# Marklin_BR_128_21MTC_Adapter.net
KiCad netlist of a schematic drawn in EAGLE
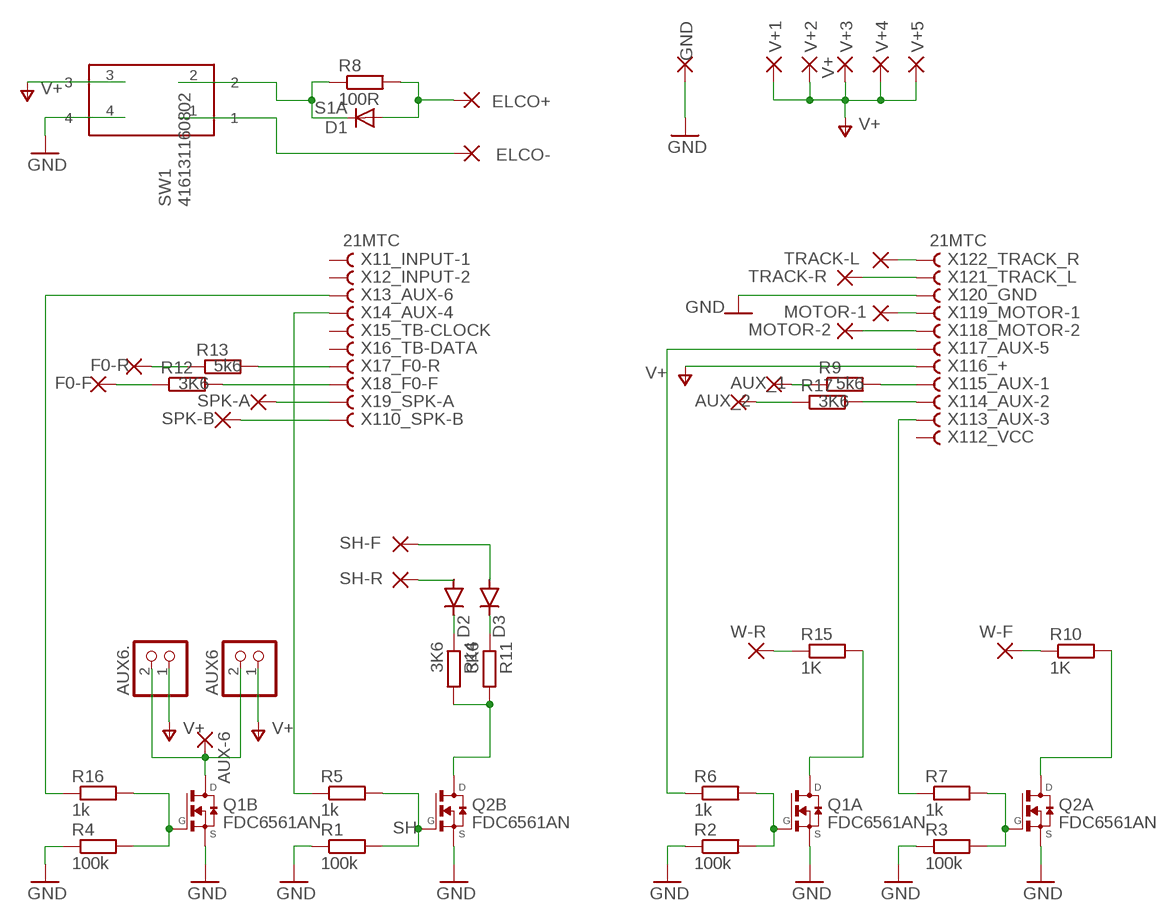
[diagram p0: schematic, sheet 1]

(export (version "E")
  (design (tool "Eeschema 10.0.6"))
  (components
    (comp (ref "AUX-6")
      (value "SMD2")
      (footprint "eagle-import:SMD1,27-2,54")
      (libsource (lib "eagle-import") (part "SMD2"))
    )
    (comp (ref "AUX6")
      (value "JST_2PIN-THM-RA")
      (footprint "eagle-import:JST-PH-2-THM-RA")
      (libsource (lib "eagle-import") (part "JST_2PIN-THM-RA"))
    )
    (comp (ref "AUX6.")
      (value "JST_2PIN-THM-RA")
      (footprint "eagle-import:JST-PH-2-THM-RA")
      (libsource (lib "eagle-import") (part "JST_2PIN-THM-RA"))
    )
    (comp (ref "AUX_1")
      (value "SMD2")
      (footprint "eagle-import:SMD1,27-2,54")
      (libsource (lib "eagle-import") (part "SMD2"))
    )
    (comp (ref "AUX_2")
      (value "SMD2")
      (footprint "eagle-import:SMD1,27-2,54")
      (libsource (lib "eagle-import") (part "SMD2"))
    )
    (comp (ref "D1")
      (value "S1A")
      (footprint "eagle-import:DO214AC")
      (fields (field (name "MF") "Fairchild"))
      (libsource (lib "eagle-import") (part "S1A"))
    )
    (comp (ref "D2")
      (value "S1M")
      (footprint "eagle-import:SMA")
      (libsource (lib "eagle-import") (part "S1M"))
    )
    (comp (ref "D3")
      (value "S1M")
      (footprint "eagle-import:SMA")
      (libsource (lib "eagle-import") (part "S1M"))
    )
    (comp (ref "ELCO+")
      (value "SMD2")
      (footprint "eagle-import:SMD1,27-2,54")
      (libsource (lib "eagle-import") (part "SMD2"))
    )
    (comp (ref "ELCO-")
      (value "SMD2")
      (footprint "eagle-import:SMD1,27-2,54")
      (libsource (lib "eagle-import") (part "SMD2"))
    )
    (comp (ref "F0-F")
      (value "SMD2")
      (footprint "eagle-import:SMD1,27-2,54")
      (libsource (lib "eagle-import") (part "SMD2"))
    )
    (comp (ref "F0-R")
      (value "SMD2")
      (footprint "eagle-import:SMD1,27-2,54")
      (libsource (lib "eagle-import") (part "SMD2"))
    )
    (comp (ref "GND")
      (value "SMD2")
      (footprint "eagle-import:SMD1,27-2,54")
      (libsource (lib "eagle-import") (part "SMD2"))
    )
    (comp (ref "MOTOR-1")
      (value "SMD2")
      (footprint "eagle-import:SMD1,27-2,54")
      (libsource (lib "eagle-import") (part "SMD2"))
    )
    (comp (ref "MOTOR-2")
      (value "SMD2")
      (footprint "eagle-import:SMD1,27-2,54")
      (libsource (lib "eagle-import") (part "SMD2"))
    )
    (comp (ref "Q1")
      (value "FDC6561AN")
      (footprint "eagle-import:SSOT-6")
      (fields (field (name "DIGI-KEY_PART_NUMBER") "FDC6561ANCT-ND") (field (name "MF") "ON Semiconductor"))
      (libsource (lib "eagle-import") (part "FDC6561AN"))
    )
    (comp (ref "Q2")
      (value "FDC6561AN")
      (footprint "eagle-import:SSOT-6")
      (fields (field (name "DIGI-KEY_PART_NUMBER") "FDC6561ANCT-ND") (field (name "MF") "ON Semiconductor"))
      (libsource (lib "eagle-import") (part "FDC6561AN"))
    )
    (comp (ref "R1")
      (value "100k")
      (footprint "eagle-import:R0603")
      (libsource (lib "eagle-import") (part "R-EU_R0603"))
    )
    (comp (ref "R2")
      (value "100k")
      (footprint "eagle-import:R0603")
      (libsource (lib "eagle-import") (part "R-EU_R0603"))
    )
    (comp (ref "R3")
      (value "100k")
      (footprint "eagle-import:R0603")
      (libsource (lib "eagle-import") (part "R-EU_R0603"))
    )
    (comp (ref "R4")
      (value "100k")
      (footprint "eagle-import:R0603")
      (libsource (lib "eagle-import") (part "R-EU_R0603"))
    )
    (comp (ref "R5")
      (value "1k")
      (footprint "eagle-import:R0603")
      (libsource (lib "eagle-import") (part "R-EU_R0603"))
    )
    (comp (ref "R6")
      (value "1k")
      (footprint "eagle-import:R0603")
      (libsource (lib "eagle-import") (part "R-EU_R0603"))
    )
    (comp (ref "R7")
      (value "1k")
      (footprint "eagle-import:R0603")
      (libsource (lib "eagle-import") (part "R-EU_R0603"))
    )
    (comp (ref "R8")
      (value "100R")
      (footprint "eagle-import:R0603")
      (libsource (lib "eagle-import") (part "R-EU_R0603"))
    )
    (comp (ref "R9")
      (value "5k6")
      (footprint "eagle-import:R0603")
      (libsource (lib "eagle-import") (part "R-EU_R0603"))
    )
    (comp (ref "R10")
      (value "1K")
      (footprint "eagle-import:R0603")
      (libsource (lib "eagle-import") (part "R-EU_R0603"))
    )
    (comp (ref "R11")
      (value "3K6")
      (footprint "eagle-import:R0603")
      (libsource (lib "eagle-import") (part "R-EU_R0603"))
    )
    (comp (ref "R12")
      (value "3K6")
      (footprint "eagle-import:R0603")
      (libsource (lib "eagle-import") (part "R-EU_R0603"))
    )
    (comp (ref "R13")
      (value "5k6")
      (footprint "eagle-import:R0603")
      (libsource (lib "eagle-import") (part "R-EU_R0603"))
    )
    (comp (ref "R14")
      (value "3K6")
      (footprint "eagle-import:R0603")
      (libsource (lib "eagle-import") (part "R-EU_R0603"))
    )
    (comp (ref "R15")
      (value "1K")
      (footprint "eagle-import:R0603")
      (libsource (lib "eagle-import") (part "R-EU_R0603"))
    )
    (comp (ref "R16")
      (value "1k")
      (footprint "eagle-import:R0603")
      (libsource (lib "eagle-import") (part "R-EU_R0603"))
    )
    (comp (ref "R17")
      (value "3K6")
      (footprint "eagle-import:R0603")
      (libsource (lib "eagle-import") (part "R-EU_R0603"))
    )
    (comp (ref "SH-F")
      (value "SH")
      (footprint "eagle-import:SMD1,27-2,54")
      (libsource (lib "eagle-import") (part "SMD2"))
    )
    (comp (ref "SH-R")
      (value "AUX-2_(SH)")
      (footprint "eagle-import:SMD1,27-2,54")
      (libsource (lib "eagle-import") (part "SMD2"))
    )
    (comp (ref "SPK-A")
      (value "SMD2")
      (footprint "eagle-import:SMD1,27-2,54")
      (libsource (lib "eagle-import") (part "SMD2"))
    )
    (comp (ref "SPK-B")
      (value "SMD2")
      (footprint "eagle-import:SMD1,27-2,54")
      (libsource (lib "eagle-import") (part "SMD2"))
    )
    (comp (ref "SW1")
      (value "416131160802")
      (footprint "eagle-import:416131160802")
      (libsource (lib "eagle-import") (part "416131160802"))
    )
    (comp (ref "TRACK-L")
      (value "SMD2")
      (footprint "eagle-import:SMD1,27-2,54")
      (libsource (lib "eagle-import") (part "SMD2"))
    )
    (comp (ref "TRACK-R")
      (value "SMD2")
      (footprint "eagle-import:SMD1,27-2,54")
      (libsource (lib "eagle-import") (part "SMD2"))
    )
    (comp (ref "V+1")
      (value "SMD2")
      (footprint "eagle-import:SMD1,27-2,54")
      (libsource (lib "eagle-import") (part "SMD2"))
    )
    (comp (ref "V+2")
      (value "SMD2")
      (footprint "eagle-import:SMD1,27-2,54")
      (libsource (lib "eagle-import") (part "SMD2"))
    )
    (comp (ref "V+3")
      (value "V+")
      (footprint "eagle-import:SMD1,27-2,54")
      (libsource (lib "eagle-import") (part "SMD2"))
    )
    (comp (ref "V+4")
      (value "SMD2")
      (footprint "eagle-import:SMD1,27-2,54")
      (libsource (lib "eagle-import") (part "SMD2"))
    )
    (comp (ref "V+5")
      (value "SMD2")
      (footprint "eagle-import:SMD1,27-2,54")
      (libsource (lib "eagle-import") (part "SMD2"))
    )
    (comp (ref "W-F")
      (value "AUX-1_(W)")
      (footprint "eagle-import:SMD1,27-2,54")
      (libsource (lib "eagle-import") (part "SMD2"))
    )
    (comp (ref "W-R")
      (value "AUX-1_(W)")
      (footprint "eagle-import:SMD1,27-2,54")
      (libsource (lib "eagle-import") (part "SMD2"))
    )
    (comp (ref "X1")
      (value "21MTC")
      (footprint "eagle-import:21MTC")
      (libsource (lib "eagle-import") (part "21MTC"))
    )
  )
  (nets
    (net (code "1") (name "GND") (class "Default")
      (node (ref "GND") (pin "1") (pinfunction "P_1") (pintype "passive"))
      (node (ref "Q1") (pin "2") (pinfunction "S_2") (pintype "passive"))
      (node (ref "Q1") (pin "5") (pinfunction "S_5") (pintype "passive"))
      (node (ref "Q2") (pin "2") (pinfunction "S_2") (pintype "passive"))
      (node (ref "Q2") (pin "5") (pinfunction "S_5") (pintype "passive"))
      (node (ref "R1") (pin "1") (pinfunction "1_1") (pintype "passive"))
      (node (ref "R2") (pin "1") (pinfunction "1_1") (pintype "passive"))
      (node (ref "R3") (pin "1") (pinfunction "1_1") (pintype "passive"))
      (node (ref "R4") (pin "1") (pinfunction "1_1") (pintype "passive"))
      (node (ref "SW1") (pin "4") (pinfunction "4_4") (pintype "bidirectional"))
      (node (ref "X1") (pin "20") (pinfunction "B_20") (pintype "passive"))
    )
    (net (code "2") (name "Net-(AUX-6-P)") (class "Default")
      (node (ref "AUX-6") (pin "1") (pinfunction "P_1") (pintype "passive"))
      (node (ref "AUX6") (pin "2") (pinfunction "1_2") (pintype "passive"))
      (node (ref "AUX6.") (pin "2") (pinfunction "1_2") (pintype "passive"))
      (node (ref "Q1") (pin "4") (pinfunction "D_4") (pintype "passive"))
    )
    (net (code "3") (name "Net-(AUX_1-P)") (class "Default")
      (node (ref "AUX_1") (pin "1") (pinfunction "P_1") (pintype "passive"))
      (node (ref "R9") (pin "1") (pinfunction "1_1") (pintype "passive"))
    )
    (net (code "4") (name "Net-(AUX_2-P)") (class "Default")
      (node (ref "AUX_2") (pin "1") (pinfunction "P_1") (pintype "passive"))
      (node (ref "R17") (pin "1") (pinfunction "1_1") (pintype "passive"))
    )
    (net (code "5") (name "Net-(D1-PadC)") (class "Default")
      (node (ref "D1") (pin "C") (pinfunction "C_C") (pintype "passive"))
      (node (ref "R8") (pin "1") (pinfunction "1_1") (pintype "passive"))
      (node (ref "SW1") (pin "2") (pinfunction "2_2") (pintype "bidirectional"))
    )
    (net (code "6") (name "Net-(D2-PadC)") (class "Default")
      (node (ref "D2") (pin "C") (pinfunction "C_C") (pintype "passive"))
      (node (ref "R14") (pin "1") (pinfunction "1_1") (pintype "passive"))
    )
    (net (code "7") (name "Net-(D3-PadC)") (class "Default")
      (node (ref "D3") (pin "C") (pinfunction "C_C") (pintype "passive"))
      (node (ref "R11") (pin "1") (pinfunction "1_1") (pintype "passive"))
    )
    (net (code "8") (name "Net-(ELCO+-P)") (class "Default")
      (node (ref "D1") (pin "A") (pinfunction "A_A") (pintype "passive"))
      (node (ref "ELCO+") (pin "1") (pinfunction "P_1") (pintype "passive"))
      (node (ref "R8") (pin "2") (pinfunction "2_2") (pintype "passive"))
    )
    (net (code "9") (name "Net-(ELCO--P)") (class "Default")
      (node (ref "ELCO-") (pin "1") (pinfunction "P_1") (pintype "passive"))
      (node (ref "SW1") (pin "1") (pinfunction "1_1") (pintype "bidirectional"))
    )
    (net (code "10") (name "Net-(F0-F-P)") (class "Default")
      (node (ref "F0-F") (pin "1") (pinfunction "P_1") (pintype "passive"))
      (node (ref "R12") (pin "1") (pinfunction "1_1") (pintype "passive"))
    )
    (net (code "11") (name "Net-(F0-R-P)") (class "Default")
      (node (ref "F0-R") (pin "1") (pinfunction "P_1") (pintype "passive"))
      (node (ref "R13") (pin "1") (pinfunction "1_1") (pintype "passive"))
    )
    (net (code "12") (name "Net-(MOTOR-1-P)") (class "Default")
      (node (ref "MOTOR-1") (pin "1") (pinfunction "P_1") (pintype "passive"))
      (node (ref "X1") (pin "19") (pinfunction "B_19") (pintype "passive"))
    )
    (net (code "13") (name "Net-(MOTOR-2-P)") (class "Default")
      (node (ref "MOTOR-2") (pin "1") (pinfunction "P_1") (pintype "passive"))
      (node (ref "X1") (pin "18") (pinfunction "B_18") (pintype "passive"))
    )
    (net (code "14") (name "Net-(Q1A-D)") (class "Default")
      (node (ref "Q1") (pin "6") (pinfunction "D_6") (pintype "passive"))
      (node (ref "R15") (pin "2") (pinfunction "2_2") (pintype "passive"))
    )
    (net (code "15") (name "Net-(Q1A-G)") (class "Default")
      (node (ref "Q1") (pin "1") (pinfunction "G_1") (pintype "passive"))
      (node (ref "R2") (pin "2") (pinfunction "2_2") (pintype "passive"))
      (node (ref "R6") (pin "2") (pinfunction "2_2") (pintype "passive"))
    )
    (net (code "16") (name "Net-(Q1B-G)") (class "Default")
      (node (ref "Q1") (pin "3") (pinfunction "G_3") (pintype "passive"))
      (node (ref "R16") (pin "2") (pinfunction "2_2") (pintype "passive"))
      (node (ref "R4") (pin "2") (pinfunction "2_2") (pintype "passive"))
    )
    (net (code "17") (name "Net-(Q2A-D)") (class "Default")
      (node (ref "Q2") (pin "6") (pinfunction "D_6") (pintype "passive"))
      (node (ref "R10") (pin "2") (pinfunction "2_2") (pintype "passive"))
    )
    (net (code "18") (name "Net-(Q2A-G)") (class "Default")
      (node (ref "Q2") (pin "1") (pinfunction "G_1") (pintype "passive"))
      (node (ref "R3") (pin "2") (pinfunction "2_2") (pintype "passive"))
      (node (ref "R7") (pin "2") (pinfunction "2_2") (pintype "passive"))
    )
    (net (code "19") (name "Net-(Q2B-D)") (class "Default")
      (node (ref "Q2") (pin "4") (pinfunction "D_4") (pintype "passive"))
      (node (ref "R11") (pin "2") (pinfunction "2_2") (pintype "passive"))
      (node (ref "R14") (pin "2") (pinfunction "2_2") (pintype "passive"))
    )
    (net (code "20") (name "Net-(Q2B-G)") (class "Default")
      (node (ref "Q2") (pin "3") (pinfunction "G_3") (pintype "passive"))
      (node (ref "R1") (pin "2") (pinfunction "2_2") (pintype "passive"))
      (node (ref "R5") (pin "2") (pinfunction "2_2") (pintype "passive"))
    )
    (net (code "21") (name "Net-(SH-F-P)") (class "Default")
      (node (ref "D3") (pin "A") (pinfunction "A_A") (pintype "passive"))
      (node (ref "SH-F") (pin "1") (pinfunction "P_1") (pintype "passive"))
    )
    (net (code "22") (name "Net-(SH-R-P)") (class "Default")
      (node (ref "D2") (pin "A") (pinfunction "A_A") (pintype "passive"))
      (node (ref "SH-R") (pin "1") (pinfunction "P_1") (pintype "passive"))
    )
    (net (code "23") (name "Net-(SPK-A-P)") (class "Default")
      (node (ref "SPK-A") (pin "1") (pinfunction "P_1") (pintype "passive"))
      (node (ref "X1") (pin "9") (pinfunction "B_9") (pintype "passive"))
    )
    (net (code "24") (name "Net-(SPK-B-P)") (class "Default")
      (node (ref "SPK-B") (pin "1") (pinfunction "P_1") (pintype "passive"))
      (node (ref "X1") (pin "10") (pinfunction "B_10") (pintype "passive"))
    )
    (net (code "25") (name "Net-(TRACK-L-P)") (class "Default")
      (node (ref "TRACK-L") (pin "1") (pinfunction "P_1") (pintype "passive"))
      (node (ref "X1") (pin "22") (pinfunction "B_22") (pintype "passive"))
    )
    (net (code "26") (name "Net-(TRACK-R-P)") (class "Default")
      (node (ref "TRACK-R") (pin "1") (pinfunction "P_1") (pintype "passive"))
      (node (ref "X1") (pin "21") (pinfunction "B_21") (pintype "passive"))
    )
    (net (code "27") (name "Net-(W-F-P)") (class "Default")
      (node (ref "R10") (pin "1") (pinfunction "1_1") (pintype "passive"))
      (node (ref "W-F") (pin "1") (pinfunction "P_1") (pintype "passive"))
    )
    (net (code "28") (name "Net-(W-R-P)") (class "Default")
      (node (ref "R15") (pin "1") (pinfunction "1_1") (pintype "passive"))
      (node (ref "W-R") (pin "1") (pinfunction "P_1") (pintype "passive"))
    )
    (net (code "29") (name "Net-(X1C-B)") (class "Default")
      (node (ref "R7") (pin "1") (pinfunction "1_1") (pintype "passive"))
      (node (ref "X1") (pin "13") (pinfunction "B_13") (pintype "passive"))
    )
    (net (code "30") (name "Net-(X1D-B)") (class "Default")
      (node (ref "R17") (pin "2") (pinfunction "2_2") (pintype "passive"))
      (node (ref "X1") (pin "14") (pinfunction "B_14") (pintype "passive"))
    )
    (net (code "31") (name "Net-(X1E-B)") (class "Default")
      (node (ref "R9") (pin "2") (pinfunction "2_2") (pintype "passive"))
      (node (ref "X1") (pin "15") (pinfunction "B_15") (pintype "passive"))
    )
    (net (code "32") (name "Net-(X1G-B)") (class "Default")
      (node (ref "R6") (pin "1") (pinfunction "1_1") (pintype "passive"))
      (node (ref "X1") (pin "17") (pinfunction "B_17") (pintype "passive"))
    )
    (net (code "33") (name "Net-(X1O-B)") (class "Default")
      (node (ref "R16") (pin "1") (pinfunction "1_1") (pintype "passive"))
      (node (ref "X1") (pin "3") (pinfunction "B_3") (pintype "passive"))
    )
    (net (code "34") (name "Net-(X1P-B)") (class "Default")
      (node (ref "R5") (pin "1") (pinfunction "1_1") (pintype "passive"))
      (node (ref "X1") (pin "4") (pinfunction "B_4") (pintype "passive"))
    )
    (net (code "35") (name "Net-(X1S-B)") (class "Default")
      (node (ref "R13") (pin "2") (pinfunction "2_2") (pintype "passive"))
      (node (ref "X1") (pin "7") (pinfunction "B_7") (pintype "passive"))
    )
    (net (code "36") (name "Net-(X1T-B)") (class "Default")
      (node (ref "R12") (pin "2") (pinfunction "2_2") (pintype "passive"))
      (node (ref "X1") (pin "8") (pinfunction "B_8") (pintype "passive"))
    )
    (net (code "37") (name "V+") (class "Default")
      (node (ref "AUX6") (pin "1") (pinfunction "2_1") (pintype "passive"))
      (node (ref "AUX6.") (pin "1") (pinfunction "2_1") (pintype "passive"))
      (node (ref "SW1") (pin "3") (pinfunction "3_3") (pintype "bidirectional"))
      (node (ref "V+1") (pin "1") (pinfunction "P_1") (pintype "passive"))
      (node (ref "V+2") (pin "1") (pinfunction "P_1") (pintype "passive"))
      (node (ref "V+3") (pin "1") (pinfunction "P_1") (pintype "passive"))
      (node (ref "V+4") (pin "1") (pinfunction "P_1") (pintype "passive"))
      (node (ref "V+5") (pin "1") (pinfunction "P_1") (pintype "passive"))
      (node (ref "X1") (pin "16") (pinfunction "B_16") (pintype "passive"))
    )
    (net (code "38") (name "unconnected-(X1B-B-Pad12)") (class "Default")
      (node (ref "X1") (pin "12") (pinfunction "B_12") (pintype "passive"))
    )
    (net (code "39") (name "unconnected-(X1J-B-Pad1)") (class "Default")
      (node (ref "X1") (pin "1") (pinfunction "B_1") (pintype "passive"))
    )
    (net (code "40") (name "unconnected-(X1N-B-Pad2)") (class "Default")
      (node (ref "X1") (pin "2") (pinfunction "B_2") (pintype "passive"))
    )
    (net (code "41") (name "unconnected-(X1Q-B-Pad5)") (class "Default")
      (node (ref "X1") (pin "5") (pinfunction "B_5") (pintype "passive"))
    )
    (net (code "42") (name "unconnected-(X1R-B-Pad6)") (class "Default")
      (node (ref "X1") (pin "6") (pinfunction "B_6") (pintype "passive"))
    )
  )
)
